# CanRadar_v1.net
KiCad netlist of a schematic drawn in Altium Designer
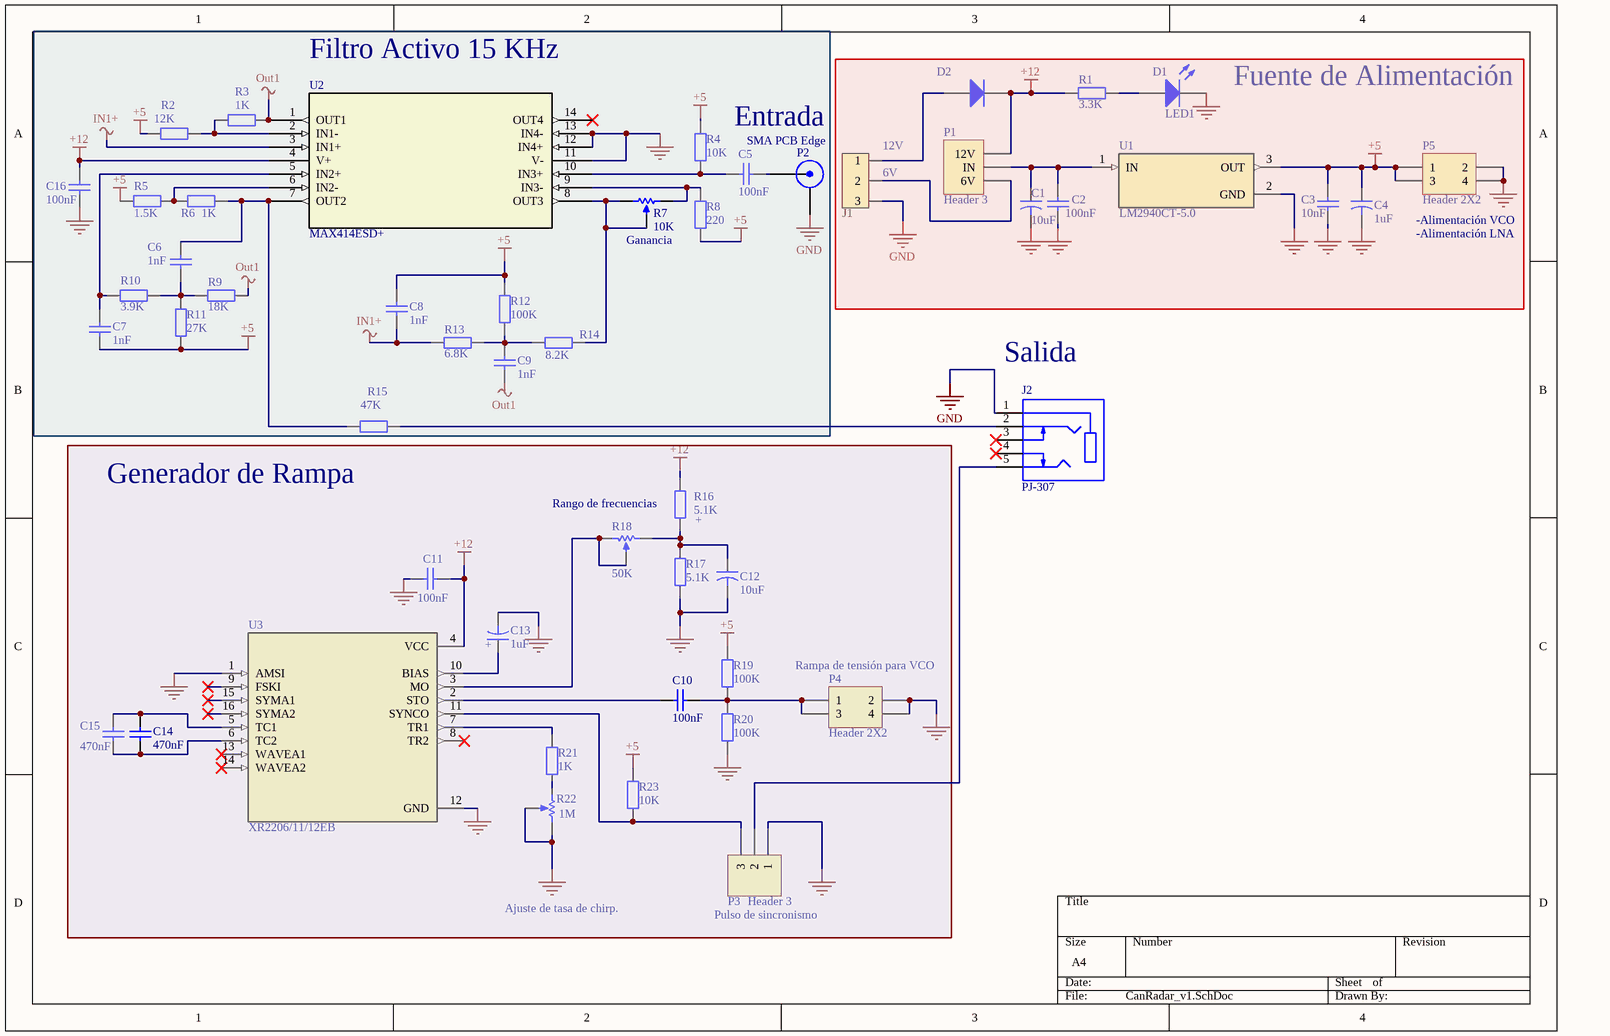
[diagram p0: CanRadar_v1.SchDoc]

(export (version "E")
  (design (tool "Eeschema 10.0.6"))
  (components
    (comp (ref "C1")
      (value "10uF")
      (footprint "CAPPR3.5-8x11.5")
      (description "Capacitor")
      (fields (field (name "Comment") "Cap2") (field (name "PUBLISHER") "Altium Limited"))
      (libsource (lib "PCB RADAR") (part "Cap2"))
    )
    (comp (ref "C2")
      (value "100nF")
      (footprint "RAD-0.2")
      (description "Capacitor")
      (fields (field (name "Comment") "Cap") (field (name "PUBLISHER") "Altium Limited"))
      (libsource (lib "PCB RADAR") (part "Cap"))
    )
    (comp (ref "C3")
      (value "10nF")
      (footprint "RAD-0.2")
      (description "Capacitor")
      (fields (field (name "Comment") "Cap") (field (name "PUBLISHER") "Altium Limited"))
      (libsource (lib "PCB RADAR") (part "Cap"))
    )
    (comp (ref "C4")
      (value "1uF")
      (footprint "CAPPR3.5-8x11.5")
      (description "Capacitor")
      (fields (field (name "Comment") "Cap2") (field (name "PUBLISHER") "Altium Limited"))
      (libsource (lib "PCB RADAR") (part "Cap2"))
    )
    (comp (ref "C5")
      (value "100nF")
      (footprint "RAD-0.2")
      (description "Capacitor")
      (fields (field (name "Comment") "Cap") (field (name "PUBLISHER") "Altium Limited"))
      (libsource (lib "PCB RADAR") (part "Cap"))
    )
    (comp (ref "C6")
      (value "1nF")
      (footprint "RAD-0.2")
      (description "Capacitor")
      (fields (field (name "Comment") "Cap") (field (name "PUBLISHER") "Altium Limited"))
      (libsource (lib "PCB RADAR") (part "Cap"))
    )
    (comp (ref "C7")
      (value "1nF")
      (footprint "RAD-0.2")
      (description "Capacitor")
      (fields (field (name "Comment") "Cap") (field (name "PUBLISHER") "Altium Limited"))
      (libsource (lib "PCB RADAR") (part "Cap"))
    )
    (comp (ref "C8")
      (value "1nF")
      (footprint "RAD-0.2")
      (description "Capacitor")
      (fields (field (name "Comment") "Cap") (field (name "PUBLISHER") "Altium Limited"))
      (libsource (lib "PCB RADAR") (part "Cap"))
    )
    (comp (ref "C9")
      (value "1nF")
      (footprint "RAD-0.2")
      (description "Capacitor")
      (fields (field (name "Comment") "Cap") (field (name "PUBLISHER") "Altium Limited"))
      (libsource (lib "PCB RADAR") (part "Cap"))
    )
    (comp (ref "C10")
      (value "100nF")
      (footprint "RAD-0.2")
      (description "Capacitor")
      (fields (field (name "Comment") "Cap") (field (name "PUBLISHER") "Altium Limited"))
      (libsource (lib "PCB RADAR") (part "Cap"))
    )
    (comp (ref "C11")
      (value "100nF")
      (footprint "RAD-0.2")
      (description "Capacitor")
      (fields (field (name "Comment") "Cap") (field (name "PUBLISHER") "Altium Limited"))
      (libsource (lib "PCB RADAR") (part "Cap"))
    )
    (comp (ref "C12")
      (value "10uF")
      (footprint "CAPPR3.5-8x11.5")
      (description "Capacitor")
      (fields (field (name "Comment") "Cap2") (field (name "PUBLISHER") "Altium Limited"))
      (libsource (lib "PCB RADAR") (part "Cap2"))
    )
    (comp (ref "C13")
      (value "1uF")
      (footprint "CAPPR3.5-8x11.5")
      (description "Capacitor")
      (fields (field (name "Comment") "Cap2") (field (name "PUBLISHER") "Altium Limited"))
      (libsource (lib "PCB RADAR") (part "Cap2"))
    )
    (comp (ref "C14")
      (value "470nF")
      (footprint "RAD-0.2")
      (description "Capacitor")
      (fields (field (name "Comment") "Cap") (field (name "PUBLISHER") "Altium Limited"))
      (libsource (lib "PCB RADAR") (part "Cap"))
    )
    (comp (ref "C15")
      (value "470nF")
      (footprint "RAD-0.2")
      (description "Capacitor")
      (fields (field (name "Comment") "Cap") (field (name "PUBLISHER") "Altium Limited"))
      (libsource (lib "PCB RADAR") (part "Cap"))
    )
    (comp (ref "C16")
      (value "100nF")
      (footprint "RAD-0.2")
      (description "Capacitor")
      (fields (field (name "Comment") "Cap") (field (name "PUBLISHER") "Altium Limited"))
      (libsource (lib "PCB RADAR") (part "Cap"))
    )
    (comp (ref "D1")
      (value "LED1")
      (footprint "LED")
      (description "Typical RED GaAs LED")
      (fields (field (name "PUBLISHER") "Altium Limited"))
      (libsource (lib "PCB RADAR") (part "LED1"))
    )
    (comp (ref "D2")
      (value "Diode 1N4001")
      (footprint "DO-41")
      (description "1 Amp General Purpose Rectifier")
      (fields (field (name "PUBLISHER") "Altium Limited"))
      (libsource (lib "PCB RADAR") (part "Diode 1N4001"))
    )
    (comp (ref "J1")
      (value "Borne x 3")
      (footprint "BORNE-3x0.2")
      (description "Triple borne para circuito impreso")
      (libsource (lib "PCB RADAR") (part "Borne x 3"))
    )
    (comp (ref "J2")
      (value "PJ-307")
      (footprint "3.5mm Jack")
      (description "3.5 mm, Stereo, Right Angle, Through Hole, Audio Jack Connector")
      (fields (field (name "MP") "SJ1-3535N") (field (name "MF") "CUI Devices"))
      (libsource (lib "PCB RADAR") (part "PJ-307"))
    )
    (comp (ref "P1")
      (value "Header 3")
      (footprint "HDR1X3")
      (description "Header, 3-Pin")
      (fields (field (name "PUBLISHER") "Altium Limited"))
      (libsource (lib "PCB RADAR") (part "Header 3"))
    )
    (comp (ref "P2")
      (value "SMA PCB Edge")
      (footprint "SMA PCB 1.6mm")
      (description "SMA conector- edge mounting -for PCB.")
      (libsource (lib "PCB RADAR") (part "SMA PCB Edge"))
    )
    (comp (ref "P3")
      (value "Header 3")
      (footprint "PCB RADAR:HDR1X3")
      (description "Header, 3-Pin")
      (fields (field (name "PUBLISHER") "Altium Limited"))
      (libsource (lib "PCB RADAR") (part "Header 3"))
    )
    (comp (ref "P4")
      (value "Header 2X2")
      (footprint "PCB RADAR:HDR2X2")
      (description "Header, 2-Pin, Dual row")
      (fields (field (name "PUBLISHER") "Altium Limited"))
      (libsource (lib "PCB RADAR") (part "Header 2X2"))
    )
    (comp (ref "P5")
      (value "Header 2X2")
      (footprint "HDR2X2")
      (description "Header, 2-Pin, Dual row")
      (fields (field (name "PUBLISHER") "Altium Limited"))
      (libsource (lib "PCB RADAR") (part "Header 2X2"))
    )
    (comp (ref "R1")
      (value "3.3K")
      (footprint "AXIAL-0.4")
      (description "Resistor")
      (fields (field (name "Comment") "Res2") (field (name "PUBLISHER") "Altium Limited"))
      (libsource (lib "") (part "Res2_3"))
    )
    (comp (ref "R2")
      (value "12K")
      (footprint "AXIAL-0.4")
      (description "Resistor")
      (fields (field (name "Comment") "Res2") (field (name "PUBLISHER") "Altium Limited"))
      (libsource (lib "") (part "Res2_1"))
    )
    (comp (ref "R3")
      (value "1K")
      (footprint "AXIAL-0.4")
      (description "Resistor")
      (fields (field (name "Comment") "Res2") (field (name "PUBLISHER") "Altium Limited"))
      (libsource (lib "") (part "Res2_1"))
    )
    (comp (ref "R4")
      (value "10K")
      (footprint "AXIAL-0.4")
      (description "Resistor")
      (fields (field (name "Comment") "Res2") (field (name "PUBLISHER") "Altium Limited"))
      (libsource (lib "") (part "Res2_2"))
    )
    (comp (ref "R5")
      (value "1.5K")
      (footprint "AXIAL-0.4")
      (description "Resistor")
      (fields (field (name "Comment") "Res2") (field (name "PUBLISHER") "Altium Limited"))
      (libsource (lib "") (part "Res2_1"))
    )
    (comp (ref "R6")
      (value "1K")
      (footprint "AXIAL-0.4")
      (description "Resistor")
      (fields (field (name "Comment") "Res2") (field (name "PUBLISHER") "Altium Limited"))
      (libsource (lib "") (part "Res2_1"))
    )
    (comp (ref "R7")
      (value "10K")
      (footprint "TRIMMER-V")
      (description "Potentiometer")
      (fields (field (name "Comment") "RPot") (field (name "PUBLISHER") "Altium Limited"))
      (libsource (lib "PCB RADAR") (part "RPot"))
    )
    (comp (ref "R8")
      (value "220")
      (footprint "AXIAL-0.4")
      (description "Resistor")
      (fields (field (name "Comment") "Res2") (field (name "PUBLISHER") "Altium Limited"))
      (libsource (lib "") (part "Res2_2"))
    )
    (comp (ref "R9")
      (value "18K")
      (footprint "AXIAL-0.4")
      (description "Resistor")
      (fields (field (name "Comment") "Res2") (field (name "PUBLISHER") "Altium Limited"))
      (libsource (lib "PCB RADAR") (part "Res2"))
    )
    (comp (ref "R10")
      (value "3.9K")
      (footprint "AXIAL-0.4")
      (description "Resistor")
      (fields (field (name "Comment") "Res2") (field (name "PUBLISHER") "Altium Limited"))
      (libsource (lib "PCB RADAR") (part "Res2"))
    )
    (comp (ref "R11")
      (value "27K")
      (footprint "AXIAL-0.4")
      (description "Resistor")
      (fields (field (name "Comment") "Res2") (field (name "PUBLISHER") "Altium Limited"))
      (libsource (lib "") (part "Res2_1"))
    )
    (comp (ref "R12")
      (value "100K")
      (footprint "AXIAL-0.4")
      (description "Resistor")
      (fields (field (name "Comment") "Res2") (field (name "PUBLISHER") "Altium Limited"))
      (libsource (lib "") (part "Res2_2"))
    )
    (comp (ref "R13")
      (value "6.8K")
      (footprint "AXIAL-0.4")
      (description "Resistor")
      (fields (field (name "Comment") "Res2") (field (name "PUBLISHER") "Altium Limited"))
      (libsource (lib "") (part "Res2_3"))
    )
    (comp (ref "R14")
      (value "8.2K")
      (footprint "AXIAL-0.4")
      (description "Resistor")
      (fields (field (name "Comment") "Res2") (field (name "PUBLISHER") "Altium Limited"))
      (libsource (lib "") (part "Res2_1"))
    )
    (comp (ref "R15")
      (value "47K")
      (footprint "AXIAL-0.4")
      (description "Resistor")
      (fields (field (name "Comment") "Res2") (field (name "PUBLISHER") "Altium Limited"))
      (libsource (lib "") (part "Res2_1"))
    )
    (comp (ref "R16")
      (value "5.1K")
      (footprint "AXIAL-0.4")
      (description "Resistor")
      (fields (field (name "Comment") "Res2") (field (name "PUBLISHER") "Altium Limited"))
      (libsource (lib "PCB RADAR") (part "Res2"))
    )
    (comp (ref "R17")
      (value "5.1K")
      (footprint "AXIAL-0.4")
      (description "Resistor")
      (fields (field (name "Comment") "Res2") (field (name "PUBLISHER") "Altium Limited"))
      (libsource (lib "PCB RADAR") (part "Res2"))
    )
    (comp (ref "R18")
      (value "50K")
      (footprint "POTE")
      (description "Potentiometer")
      (fields (field (name "Comment") "RPot") (field (name "PUBLISHER") "Altium Limited"))
      (libsource (lib "PCB RADAR") (part "RPot"))
    )
    (comp (ref "R19")
      (value "100K")
      (footprint "AXIAL-0.4")
      (description "Resistor")
      (fields (field (name "Comment") "Res2") (field (name "PUBLISHER") "Altium Limited"))
      (libsource (lib "") (part "Res2_2"))
    )
    (comp (ref "R20")
      (value "100K")
      (footprint "AXIAL-0.4")
      (description "Resistor")
      (fields (field (name "Comment") "Res2") (field (name "PUBLISHER") "Altium Limited"))
      (libsource (lib "") (part "Res2_2"))
    )
    (comp (ref "R21")
      (value "1K")
      (footprint "AXIAL-0.4")
      (description "Resistor")
      (fields (field (name "Comment") "Res2") (field (name "PUBLISHER") "Altium Limited"))
      (libsource (lib "") (part "Res2_2"))
    )
    (comp (ref "R22")
      (value "1M")
      (footprint "POTE")
      (description "Potentiometer")
      (fields (field (name "Comment") "RPot") (field (name "PUBLISHER") "Altium Limited"))
      (libsource (lib "PCB RADAR") (part "RPot"))
    )
    (comp (ref "R23")
      (value "10K")
      (footprint "AXIAL-0.4")
      (description "Resistor")
      (fields (field (name "Comment") "Res2") (field (name "PUBLISHER") "Altium Limited"))
      (libsource (lib "PCB RADAR") (part "Res2"))
    )
    (comp (ref "U1")
      (value "LM2940CT-5.0")
      (footprint "TO254P1054X470X1955-3")
      (description "1-A, 26-V, high-PSRR, low-dropout voltage regulator 3-TO-220 0 to 125")
      (fields
        (field (name "MF") "Texas Instruments")
        (field (name "BUYPART") "https://www.snapeda.com/parts/LM2940CT-5.0/Texas%20Instruments/view-part/213981/?ref=eda")
      )
      (libsource (lib "PCB RADAR") (part "LM2940CT-5.0"))
    )
    (comp (ref "U2")
      (value "MAX414ESD+")
      (footprint "21-0041B_14_MXM-M")
      (description "No Description Available")
      (fields (field (name "COPYRIGHT") "Copyright (C) 2022 Ultra Librarian. All rights reserved."))
      (libsource (lib "PCB RADAR") (part "MAX414ESD+"))
    )
    (comp (ref "U3")
      (value "XR2206/11/12EB")
      (footprint "DIP-16")
      (description "XR2206, XR2211, XR2212 Multi-Purpose Timing Evaluation Board")
      (fields (field (name "MF") "MaxLinear, Inc.") (field (name "DIGI-KEY_PART_NUMBER") "1016-1428-ND"))
      (libsource (lib "PCB RADAR") (part "XR2206/11/12EB"))
    )
  )
  (nets
    (net (code "1") (name "+5") (class "Default")
      (node (ref "C3") (pin "1") (pinfunction "1_1") (pintype "passive"))
      (node (ref "C4") (pin "2") (pinfunction "-_2") (pintype "passive"))
      (node (ref "C7") (pin "2") (pinfunction "2_2") (pintype "passive"))
      (node (ref "C8") (pin "1") (pinfunction "1_1") (pintype "passive"))
      (node (ref "P5") (pin "1") (pinfunction "1_1") (pintype "passive"))
      (node (ref "P5") (pin "3") (pinfunction "3_3") (pintype "passive"))
      (node (ref "R11") (pin "1") (pinfunction "1_1") (pintype "passive"))
      (node (ref "R12") (pin "2") (pinfunction "2_2") (pintype "passive"))
      (node (ref "R19") (pin "2") (pinfunction "2_2") (pintype "passive"))
      (node (ref "R2") (pin "1") (pinfunction "1_1") (pintype "passive"))
      (node (ref "R23") (pin "1") (pinfunction "1_1") (pintype "passive"))
      (node (ref "R4") (pin "2") (pinfunction "2_2") (pintype "passive"))
      (node (ref "R5") (pin "1") (pinfunction "1_1") (pintype "passive"))
      (node (ref "R8") (pin "1") (pinfunction "1_1") (pintype "passive"))
      (node (ref "U1") (pin "3") (pinfunction "OUT_3") (pintype "output"))
    )
    (net (code "2") (name "+12") (class "Default")
      (node (ref "C11") (pin "2") (pinfunction "2_2") (pintype "passive"))
      (node (ref "C16") (pin "1") (pinfunction "1_1") (pintype "passive"))
      (node (ref "D2") (pin "2") (pinfunction "K_2") (pintype "passive"))
      (node (ref "P1") (pin "1") (pinfunction "12V_1") (pintype "passive"))
      (node (ref "R1") (pin "2") (pinfunction "2_2") (pintype "passive"))
      (node (ref "R16") (pin "1") (pinfunction "1_1") (pintype "passive"))
      (node (ref "U2") (pin "4") (pinfunction "V+_4") (pintype "power_in"))
      (node (ref "U3") (pin "4") (pinfunction "VCC_4") (pintype "power_in"))
    )
    (net (code "3") (name "GND") (class "Default")
      (node (ref "C1") (pin "1") (pinfunction "+_1") (pintype "passive"))
      (node (ref "C11") (pin "1") (pinfunction "1_1") (pintype "passive"))
      (node (ref "C12") (pin "1") (pinfunction "+_1") (pintype "passive"))
      (node (ref "C13") (pin "1") (pinfunction "+_1") (pintype "passive"))
      (node (ref "C16") (pin "2") (pinfunction "2_2") (pintype "passive"))
      (node (ref "C2") (pin "2") (pinfunction "2_2") (pintype "passive"))
      (node (ref "C3") (pin "2") (pinfunction "2_2") (pintype "passive"))
      (node (ref "C4") (pin "1") (pinfunction "+_1") (pintype "passive"))
      (node (ref "D1") (pin "2") (pinfunction "K_2") (pintype "passive"))
      (node (ref "J1") (pin "3") (pinfunction "3_3") (pintype "passive"))
      (node (ref "J2") (pin "1") (pinfunction "1_1") (pintype "passive"))
      (node (ref "P2") (pin "2") (pinfunction "Y_2") (pintype "passive"))
      (node (ref "P3") (pin "1") (pinfunction "12V_1") (pintype "passive"))
      (node (ref "P4") (pin "2") (pinfunction "2_2") (pintype "passive"))
      (node (ref "P4") (pin "4") (pinfunction "4_4") (pintype "passive"))
      (node (ref "P5") (pin "2") (pinfunction "2_2") (pintype "passive"))
      (node (ref "P5") (pin "4") (pinfunction "4_4") (pintype "passive"))
      (node (ref "R17") (pin "2") (pinfunction "2_2") (pintype "passive"))
      (node (ref "R20") (pin "1") (pinfunction "1_1") (pintype "passive"))
      (node (ref "R22") (pin "2") (pinfunction "BOT_2") (pintype "passive"))
      (node (ref "R22") (pin "3") (pinfunction "TAP_3") (pintype "passive"))
      (node (ref "U1") (pin "2") (pinfunction "GND_2") (pintype "power_in"))
      (node (ref "U2") (pin "11") (pinfunction "V-_11") (pintype "power_in"))
      (node (ref "U2") (pin "12") (pinfunction "IN4+_12") (pintype "input"))
      (node (ref "U2") (pin "13") (pinfunction "IN4-_13") (pintype "input"))
      (node (ref "U3") (pin "1") (pinfunction "AMSI_1") (pintype "input"))
      (node (ref "U3") (pin "12") (pinfunction "GND_12") (pintype "power_in"))
    )
    (net (code "4") (name "IN1+") (class "Default")
      (node (ref "C8") (pin "2") (pinfunction "2_2") (pintype "passive"))
      (node (ref "R13") (pin "2") (pinfunction "2_2") (pintype "passive"))
      (node (ref "U2") (pin "3") (pinfunction "IN1+_3") (pintype "input"))
    )
    (net (code "5") (name "Net-(C1--)") (class "Default")
      (node (ref "C1") (pin "2") (pinfunction "-_2") (pintype "passive"))
      (node (ref "C2") (pin "1") (pinfunction "1_1") (pintype "passive"))
      (node (ref "P1") (pin "2") (pinfunction "IN_2") (pintype "passive"))
      (node (ref "U1") (pin "1") (pinfunction "IN_1") (pintype "input"))
    )
    (net (code "6") (name "Net-(C6-Pad2)") (class "Default")
      (node (ref "C6") (pin "2") (pinfunction "2_2") (pintype "passive"))
      (node (ref "R10") (pin "1") (pinfunction "1_1") (pintype "passive"))
      (node (ref "R11") (pin "2") (pinfunction "2_2") (pintype "passive"))
      (node (ref "R9") (pin "2") (pinfunction "2_2") (pintype "passive"))
    )
    (net (code "7") (name "Net-(C9-Pad1)") (class "Default")
      (node (ref "C9") (pin "1") (pinfunction "1_1") (pintype "passive"))
      (node (ref "R12") (pin "1") (pinfunction "1_1") (pintype "passive"))
      (node (ref "R13") (pin "1") (pinfunction "1_1") (pintype "passive"))
      (node (ref "R14") (pin "1") (pinfunction "1_1") (pintype "passive"))
    )
    (net (code "8") (name "Net-(C10-Pad2)") (class "Default")
      (node (ref "C10") (pin "2") (pinfunction "2_2") (pintype "passive"))
      (node (ref "P4") (pin "1") (pinfunction "1_1") (pintype "passive"))
      (node (ref "P4") (pin "3") (pinfunction "3_3") (pintype "passive"))
      (node (ref "R19") (pin "1") (pinfunction "1_1") (pintype "passive"))
      (node (ref "R20") (pin "2") (pinfunction "2_2") (pintype "passive"))
    )
    (net (code "9") (name "Net-(C12--)") (class "Default")
      (node (ref "C12") (pin "2") (pinfunction "-_2") (pintype "passive"))
      (node (ref "R16") (pin "2") (pinfunction "2_2") (pintype "passive"))
      (node (ref "R17") (pin "1") (pinfunction "1_1") (pintype "passive"))
      (node (ref "R18") (pin "1") (pinfunction "TOP_1") (pintype "passive"))
    )
    (net (code "10") (name "Net-(C13--)") (class "Default")
      (node (ref "C13") (pin "2") (pinfunction "-_2") (pintype "passive"))
      (node (ref "U3") (pin "10") (pinfunction "BIAS_10") (pintype "output"))
    )
    (net (code "11") (name "Net-(D1-A)") (class "Default")
      (node (ref "D1") (pin "1") (pinfunction "A_1") (pintype "passive"))
      (node (ref "R1") (pin "1") (pinfunction "1_1") (pintype "passive"))
    )
    (net (code "12") (name "Net-(D2-A)") (class "Default")
      (node (ref "D2") (pin "1") (pinfunction "A_1") (pintype "passive"))
      (node (ref "J1") (pin "1") (pinfunction "1_1") (pintype "passive"))
    )
    (net (code "13") (name "Net-(J2-Pad2)") (class "Default")
      (node (ref "J2") (pin "2") (pinfunction "2_2") (pintype "passive"))
      (node (ref "R15") (pin "2") (pinfunction "2_2") (pintype "passive"))
    )
    (net (code "14") (name "Net-(P1-6V)") (class "Default")
      (node (ref "J1") (pin "2") (pinfunction "2_2") (pintype "passive"))
      (node (ref "P1") (pin "3") (pinfunction "6V_3") (pintype "passive"))
    )
    (net (code "15") (name "Net-(P2-X)") (class "Default")
      (node (ref "C5") (pin "2") (pinfunction "2_2") (pintype "passive"))
      (node (ref "P2") (pin "1") (pinfunction "X_1") (pintype "passive"))
    )
    (net (code "16") (name "Net-(P3-6V)") (class "Default")
      (node (ref "P3") (pin "3") (pinfunction "6V_3") (pintype "passive"))
      (node (ref "R23") (pin "2") (pinfunction "2_2") (pintype "passive"))
      (node (ref "U3") (pin "11") (pinfunction "SYNCO_11") (pintype "output"))
    )
    (net (code "17") (name "Net-(P3-IN)") (class "Default")
      (node (ref "J2") (pin "5") (pinfunction "5_5") (pintype "passive"))
      (node (ref "P3") (pin "2") (pinfunction "IN_2") (pintype "passive"))
    )
    (net (code "18") (name "Net-(R7-BOT)") (class "Default")
      (node (ref "R7") (pin "2") (pinfunction "BOT_2") (pintype "passive"))
      (node (ref "R8") (pin "2") (pinfunction "2_2") (pintype "passive"))
      (node (ref "U2") (pin "9") (pinfunction "IN3-_9") (pintype "input"))
    )
    (net (code "19") (name "Net-(R7-TAP)") (class "Default")
      (node (ref "R14") (pin "2") (pinfunction "2_2") (pintype "passive"))
      (node (ref "R7") (pin "1") (pinfunction "TOP_1") (pintype "passive"))
      (node (ref "R7") (pin "3") (pinfunction "TAP_3") (pintype "passive"))
      (node (ref "U2") (pin "8") (pinfunction "OUT3_8") (pintype "output"))
    )
    (net (code "20") (name "Net-(R18-BOT)") (class "Default")
      (node (ref "R18") (pin "2") (pinfunction "BOT_2") (pintype "passive"))
      (node (ref "R18") (pin "3") (pinfunction "TAP_3") (pintype "passive"))
      (node (ref "U3") (pin "3") (pinfunction "MO_3") (pintype "output"))
    )
    (net (code "21") (name "Net-(R22-TOP)") (class "Default")
      (node (ref "R21") (pin "1") (pinfunction "1_1") (pintype "passive"))
      (node (ref "R22") (pin "1") (pinfunction "TOP_1") (pintype "passive"))
    )
    (net (code "22") (name "Net-(U2-IN1-)") (class "Default")
      (node (ref "R2") (pin "2") (pinfunction "2_2") (pintype "passive"))
      (node (ref "R3") (pin "1") (pinfunction "1_1") (pintype "passive"))
      (node (ref "U2") (pin "2") (pinfunction "IN1-_2") (pintype "input"))
    )
    (net (code "23") (name "Net-(U2-IN2+)") (class "Default")
      (node (ref "C7") (pin "1") (pinfunction "1_1") (pintype "passive"))
      (node (ref "R10") (pin "2") (pinfunction "2_2") (pintype "passive"))
      (node (ref "U2") (pin "5") (pinfunction "IN2+_5") (pintype "input"))
    )
    (net (code "24") (name "Net-(U2-IN2-)") (class "Default")
      (node (ref "R5") (pin "2") (pinfunction "2_2") (pintype "passive"))
      (node (ref "R6") (pin "1") (pinfunction "1_1") (pintype "passive"))
      (node (ref "U2") (pin "6") (pinfunction "IN2-_6") (pintype "input"))
    )
    (net (code "25") (name "Net-(U2-IN3+)") (class "Default")
      (node (ref "C5") (pin "1") (pinfunction "1_1") (pintype "passive"))
      (node (ref "R4") (pin "1") (pinfunction "1_1") (pintype "passive"))
      (node (ref "U2") (pin "10") (pinfunction "IN3+_10") (pintype "input"))
    )
    (net (code "26") (name "Net-(U2-OUT2)") (class "Default")
      (node (ref "C6") (pin "1") (pinfunction "1_1") (pintype "passive"))
      (node (ref "R15") (pin "1") (pinfunction "1_1") (pintype "passive"))
      (node (ref "R6") (pin "2") (pinfunction "2_2") (pintype "passive"))
      (node (ref "U2") (pin "7") (pinfunction "OUT2_7") (pintype "output"))
    )
    (net (code "27") (name "Net-(U3-STO)") (class "Default")
      (node (ref "C10") (pin "1") (pinfunction "1_1") (pintype "passive"))
      (node (ref "U3") (pin "2") (pinfunction "STO_2") (pintype "output"))
    )
    (net (code "28") (name "Net-(U3-TC1)") (class "Default")
      (node (ref "C14") (pin "2") (pinfunction "2_2") (pintype "passive"))
      (node (ref "C15") (pin "1") (pinfunction "1_1") (pintype "passive"))
      (node (ref "U3") (pin "5") (pinfunction "TC1_5") (pintype "input"))
    )
    (net (code "29") (name "Net-(U3-TC2)") (class "Default")
      (node (ref "C14") (pin "1") (pinfunction "1_1") (pintype "passive"))
      (node (ref "C15") (pin "2") (pinfunction "2_2") (pintype "passive"))
      (node (ref "U3") (pin "6") (pinfunction "TC2_6") (pintype "input"))
    )
    (net (code "30") (name "Net-(U3-TR1)") (class "Default")
      (node (ref "R21") (pin "2") (pinfunction "2_2") (pintype "passive"))
      (node (ref "U3") (pin "7") (pinfunction "TR1_7") (pintype "output"))
    )
    (net (code "31") (name "Out1") (class "Default")
      (node (ref "C9") (pin "2") (pinfunction "2_2") (pintype "passive"))
      (node (ref "R3") (pin "2") (pinfunction "2_2") (pintype "passive"))
      (node (ref "R9") (pin "1") (pinfunction "1_1") (pintype "passive"))
      (node (ref "U2") (pin "1") (pinfunction "OUT1_1") (pintype "output"))
    )
    (net (code "32") (name "unconnected-(J2-Pad3)") (class "Default")
      (node (ref "J2") (pin "3") (pinfunction "3_3") (pintype "passive+no_connect"))
    )
    (net (code "33") (name "unconnected-(J2-Pad4)") (class "Default")
      (node (ref "J2") (pin "4") (pinfunction "4_4") (pintype "passive+no_connect"))
    )
    (net (code "34") (name "unconnected-(U2-OUT4-Pad14)") (class "Default")
      (node (ref "U2") (pin "14") (pinfunction "OUT4_14") (pintype "output+no_connect"))
    )
    (net (code "35") (name "unconnected-(U3-FSKI-Pad9)") (class "Default")
      (node (ref "U3") (pin "9") (pinfunction "FSKI_9") (pintype "input+no_connect"))
    )
    (net (code "36") (name "unconnected-(U3-SYMA1-Pad15)") (class "Default")
      (node (ref "U3") (pin "15") (pinfunction "SYMA1_15") (pintype "input+no_connect"))
    )
    (net (code "37") (name "unconnected-(U3-SYMA2-Pad16)") (class "Default")
      (node (ref "U3") (pin "16") (pinfunction "SYMA2_16") (pintype "input+no_connect"))
    )
    (net (code "38") (name "unconnected-(U3-TR2-Pad8)") (class "Default")
      (node (ref "U3") (pin "8") (pinfunction "TR2_8") (pintype "output+no_connect"))
    )
    (net (code "39") (name "unconnected-(U3-WAVEA1-Pad13)") (class "Default")
      (node (ref "U3") (pin "13") (pinfunction "WAVEA1_13") (pintype "input+no_connect"))
    )
    (net (code "40") (name "unconnected-(U3-WAVEA2-Pad14)") (class "Default")
      (node (ref "U3") (pin "14") (pinfunction "WAVEA2_14") (pintype "input+no_connect"))
    )
  )
)
